# NT_SolarModule1.net
KiCad netlist of a schematic drawn in EAGLE
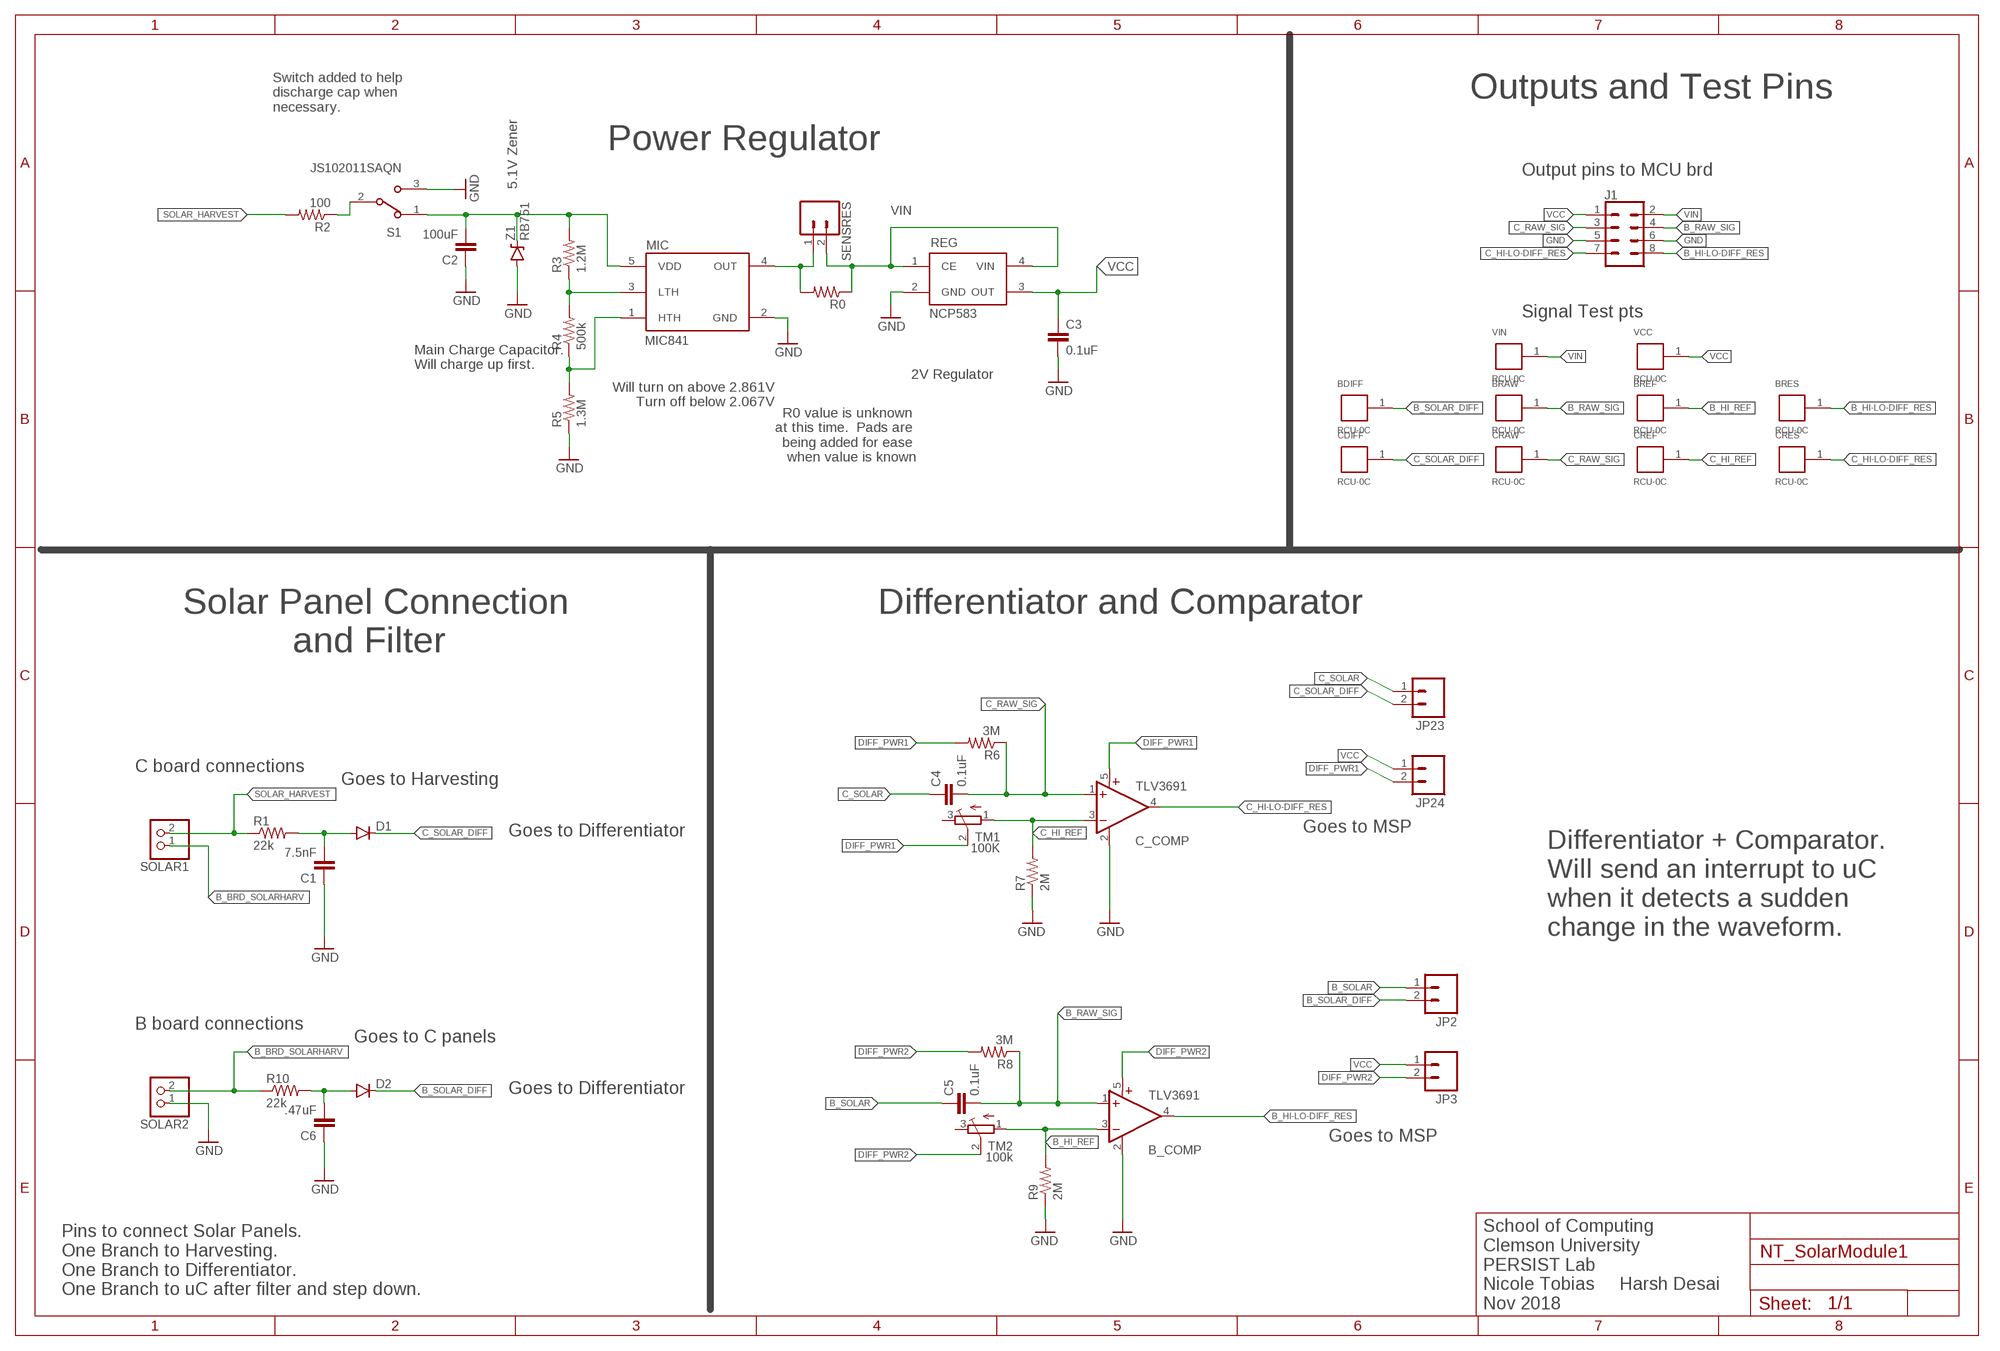
[diagram p0: schematic, sheet 1]

(export (version "E")
  (design (tool "Eeschema 10.0.6"))
  (components
    (comp (ref "BDIFF")
      (value "RCU-0C")
      (footprint "eagle-import:TE_RCU-0C")
      (fields
        (field (name "COMMENT") "RCU-0C _1625854-3_")
        (field (name "MF") "TE Connectivity")
        (field (name "TOLERANCE") "0%")
      )
      (libsource (lib "eagle-import") (part "RCU-0C"))
    )
    (comp (ref "BRAW")
      (value "RCU-0C")
      (footprint "eagle-import:TE_RCU-0C")
      (fields
        (field (name "COMMENT") "RCU-0C _1625854-3_")
        (field (name "MF") "TE Connectivity")
        (field (name "TOLERANCE") "0%")
      )
      (libsource (lib "eagle-import") (part "RCU-0C"))
    )
    (comp (ref "BREF")
      (value "RCU-0C")
      (footprint "eagle-import:TE_RCU-0C")
      (fields
        (field (name "COMMENT") "RCU-0C _1625854-3_")
        (field (name "MF") "TE Connectivity")
        (field (name "TOLERANCE") "0%")
      )
      (libsource (lib "eagle-import") (part "RCU-0C"))
    )
    (comp (ref "BRES")
      (value "RCU-0C")
      (footprint "eagle-import:TE_RCU-0C")
      (fields
        (field (name "COMMENT") "RCU-0C _1625854-3_")
        (field (name "MF") "TE Connectivity")
        (field (name "TOLERANCE") "0%")
      )
      (libsource (lib "eagle-import") (part "RCU-0C"))
    )
    (comp (ref "B_COMP")
      (value "TLV3691")
      (footprint "eagle-import:SC70-5")
      (libsource (lib "eagle-import") (part "TLV3691"))
    )
    (comp (ref "C1")
      (value "7.5nF")
      (footprint "eagle-import:0603-CAP")
      (libsource (lib "eagle-import") (part "CAP0603-CAP"))
    )
    (comp (ref "C2")
      (value "100uF")
      (footprint "eagle-import:0603-CAP")
      (libsource (lib "eagle-import") (part "CAP0603-CAP"))
    )
    (comp (ref "C3")
      (value "0.1uF")
      (footprint "eagle-import:0603-CAP")
      (libsource (lib "eagle-import") (part "CAP0603-CAP"))
    )
    (comp (ref "C4")
      (value "0.1uF")
      (footprint "eagle-import:0603-CAP")
      (libsource (lib "eagle-import") (part "CAP0603-CAP"))
    )
    (comp (ref "C5")
      (value "0.1uF")
      (footprint "eagle-import:0603-CAP")
      (libsource (lib "eagle-import") (part "CAP0603-CAP"))
    )
    (comp (ref "C6")
      (value ".47uF")
      (footprint "eagle-import:0603-CAP")
      (libsource (lib "eagle-import") (part "CAP0603-CAP"))
    )
    (comp (ref "CDIFF")
      (value "RCU-0C")
      (footprint "eagle-import:TE_RCU-0C")
      (fields
        (field (name "COMMENT") "RCU-0C _1625854-3_")
        (field (name "MF") "TE Connectivity")
        (field (name "TOLERANCE") "0%")
      )
      (libsource (lib "eagle-import") (part "RCU-0C"))
    )
    (comp (ref "CRAW")
      (value "RCU-0C")
      (footprint "eagle-import:TE_RCU-0C")
      (fields
        (field (name "COMMENT") "RCU-0C _1625854-3_")
        (field (name "MF") "TE Connectivity")
        (field (name "TOLERANCE") "0%")
      )
      (libsource (lib "eagle-import") (part "RCU-0C"))
    )
    (comp (ref "CREF")
      (value "RCU-0C")
      (footprint "eagle-import:TE_RCU-0C")
      (fields
        (field (name "COMMENT") "RCU-0C _1625854-3_")
        (field (name "MF") "TE Connectivity")
        (field (name "TOLERANCE") "0%")
      )
      (libsource (lib "eagle-import") (part "RCU-0C"))
    )
    (comp (ref "CRES")
      (value "RCU-0C")
      (footprint "eagle-import:TE_RCU-0C")
      (fields
        (field (name "COMMENT") "RCU-0C _1625854-3_")
        (field (name "MF") "TE Connectivity")
        (field (name "TOLERANCE") "0%")
      )
      (libsource (lib "eagle-import") (part "RCU-0C"))
    )
    (comp (ref "C_COMP")
      (value "TLV3691")
      (footprint "eagle-import:SC70-5")
      (libsource (lib "eagle-import") (part "TLV3691"))
    )
    (comp (ref "D1")
      (value "DIODESOD523")
      (footprint "eagle-import:SOD523")
      (libsource (lib "eagle-import") (part "DIODESOD523"))
    )
    (comp (ref "D2")
      (value "DIODESOD523")
      (footprint "eagle-import:SOD523")
      (libsource (lib "eagle-import") (part "DIODESOD523"))
    )
    (comp (ref "J1")
      (value "CONN_04X2")
      (footprint "eagle-import:2X4")
      (libsource (lib "eagle-import") (part "CONN_04X2"))
    )
    (comp (ref "JP2")
      (value "M02")
      (footprint "eagle-import:1X02-1.27MM")
      (libsource (lib "eagle-import") (part "M02"))
    )
    (comp (ref "JP3")
      (value "M02")
      (footprint "eagle-import:1X02-1.27MM")
      (libsource (lib "eagle-import") (part "M02"))
    )
    (comp (ref "JP23")
      (value "M02")
      (footprint "eagle-import:1X02-1.27MM")
      (libsource (lib "eagle-import") (part "M02"))
    )
    (comp (ref "JP24")
      (value "M02")
      (footprint "eagle-import:1X02-1.27MM")
      (libsource (lib "eagle-import") (part "M02"))
    )
    (comp (ref "MIC")
      (value "MIC841")
      (footprint "eagle-import:SC70-5")
      (libsource (lib "eagle-import") (part "MIC841"))
    )
    (comp (ref "R0")
      (value "RESISTOR0603")
      (footprint "eagle-import:0603-RES")
      (libsource (lib "eagle-import") (part "RESISTOR0603"))
    )
    (comp (ref "R1")
      (value "22k")
      (footprint "eagle-import:0603-RES")
      (libsource (lib "eagle-import") (part "RESISTOR0603"))
    )
    (comp (ref "R2")
      (value "100")
      (footprint "eagle-import:0603-RES")
      (libsource (lib "eagle-import") (part "RESISTOR0603"))
    )
    (comp (ref "R3")
      (value "1.2M")
      (footprint "eagle-import:0603-RES")
      (libsource (lib "eagle-import") (part "RESISTOR0603"))
    )
    (comp (ref "R4")
      (value "500k")
      (footprint "eagle-import:0603-RES")
      (libsource (lib "eagle-import") (part "RESISTOR0603"))
    )
    (comp (ref "R5")
      (value "1.3M")
      (footprint "eagle-import:0603-RES")
      (libsource (lib "eagle-import") (part "RESISTOR0603"))
    )
    (comp (ref "R6")
      (value "3M")
      (footprint "eagle-import:0603-RES")
      (libsource (lib "eagle-import") (part "RESISTOR0603"))
    )
    (comp (ref "R7")
      (value "2M")
      (footprint "eagle-import:0603-RES")
      (libsource (lib "eagle-import") (part "RESISTOR0603"))
    )
    (comp (ref "R8")
      (value "3M")
      (footprint "eagle-import:0603-RES")
      (libsource (lib "eagle-import") (part "RESISTOR0603"))
    )
    (comp (ref "R9")
      (value "2M")
      (footprint "eagle-import:0603-RES")
      (libsource (lib "eagle-import") (part "RESISTOR0603"))
    )
    (comp (ref "R10")
      (value "22k")
      (footprint "eagle-import:0603-RES")
      (libsource (lib "eagle-import") (part "RESISTOR0603"))
    )
    (comp (ref "REG")
      (value "NCP583")
      (footprint "eagle-import:SC82-AB_1PRIMARY")
      (libsource (lib "eagle-import") (part "NCP583"))
    )
    (comp (ref "S1")
      (value "JS102011SAQN")
      (footprint "eagle-import:SW_JS102011SAQN")
      (fields (field (name "MF") "C&K Components"))
      (libsource (lib "eagle-import") (part "JS102011SAQN"))
    )
    (comp (ref "SENSRES")
      (value "CONN_02")
      (footprint "eagle-import:1X02")
      (libsource (lib "eagle-import") (part "CONN_02"))
    )
    (comp (ref "SOLAR1")
      (value "PINHD-1X2")
      (footprint "eagle-import:1X02")
      (libsource (lib "eagle-import") (part "PINHD-1X2"))
    )
    (comp (ref "SOLAR2")
      (value "PINHD-1X2")
      (footprint "eagle-import:1X02")
      (libsource (lib "eagle-import") (part "PINHD-1X2"))
    )
    (comp (ref "TM1")
      (value "100K")
      (footprint "eagle-import:TC33X")
      (libsource (lib "eagle-import") (part "TRIMPOTTC33X"))
    )
    (comp (ref "TM2")
      (value "100k")
      (footprint "eagle-import:TC33X")
      (libsource (lib "eagle-import") (part "TRIMPOTTC33X"))
    )
    (comp (ref "VCC")
      (value "RCU-0C")
      (footprint "eagle-import:TE_RCU-0C")
      (fields
        (field (name "COMMENT") "RCU-0C _1625854-3_")
        (field (name "MF") "TE Connectivity")
        (field (name "TOLERANCE") "0%")
      )
      (libsource (lib "eagle-import") (part "RCU-0C"))
    )
    (comp (ref "VIN")
      (value "RCU-0C")
      (footprint "eagle-import:TE_RCU-0C")
      (fields
        (field (name "COMMENT") "RCU-0C _1625854-3_")
        (field (name "MF") "TE Connectivity")
        (field (name "TOLERANCE") "0%")
      )
      (libsource (lib "eagle-import") (part "RCU-0C"))
    )
    (comp (ref "Z1")
      (value "RB751")
      (footprint "eagle-import:SOD-523")
      (libsource (lib "eagle-import") (part "DIODE-ZENER"))
    )
  )
  (nets
    (net (code "1") (name "B_BRD_SOLARHARV") (class "Default")
      (node (ref "R10") (pin "1") (pinfunction "1_1") (pintype "passive"))
      (node (ref "SOLAR1") (pin "1") (pinfunction "1_1") (pintype "passive"))
      (node (ref "SOLAR2") (pin "2") (pinfunction "2_2") (pintype "passive"))
    )
    (net (code "2") (name "B_HI-LO-DIFF_RES") (class "Default")
      (node (ref "BRES") (pin "1") (pinfunction "1_1") (pintype "passive"))
      (node (ref "B_COMP") (pin "4") (pinfunction "OUT_4") (pintype "output"))
      (node (ref "J1") (pin "8") (pinfunction "8_8") (pintype "passive"))
    )
    (net (code "3") (name "B_HI_REF") (class "Default")
      (node (ref "BREF") (pin "1") (pinfunction "1_1") (pintype "passive"))
      (node (ref "B_COMP") (pin "3") (pinfunction "-IN_3") (pintype "input"))
      (node (ref "R9") (pin "2") (pinfunction "2_2") (pintype "passive"))
      (node (ref "TM2") (pin "1") (pinfunction "A_1") (pintype "passive"))
    )
    (net (code "4") (name "B_RAW_SIG") (class "Default")
      (node (ref "BRAW") (pin "1") (pinfunction "1_1") (pintype "passive"))
      (node (ref "B_COMP") (pin "1") (pinfunction "+IN_1") (pintype "input"))
      (node (ref "C5") (pin "2") (pinfunction "2_2") (pintype "passive"))
      (node (ref "J1") (pin "4") (pinfunction "4_4") (pintype "passive"))
      (node (ref "R8") (pin "1") (pinfunction "1_1") (pintype "passive"))
    )
    (net (code "5") (name "B_SOLAR") (class "Default")
      (node (ref "C5") (pin "1") (pinfunction "1_1") (pintype "passive"))
      (node (ref "JP2") (pin "1") (pinfunction "1_1") (pintype "passive"))
    )
    (net (code "6") (name "B_SOLAR_DIFF") (class "Default")
      (node (ref "BDIFF") (pin "1") (pinfunction "1_1") (pintype "passive"))
      (node (ref "D2") (pin "C") (pinfunction "C_C") (pintype "passive"))
      (node (ref "JP2") (pin "2") (pinfunction "2_2") (pintype "passive"))
    )
    (net (code "7") (name "C_HI-LO-DIFF_RES") (class "Default")
      (node (ref "CRES") (pin "1") (pinfunction "1_1") (pintype "passive"))
      (node (ref "C_COMP") (pin "4") (pinfunction "OUT_4") (pintype "output"))
      (node (ref "J1") (pin "7") (pinfunction "7_7") (pintype "passive"))
    )
    (net (code "8") (name "C_HI_REF") (class "Default")
      (node (ref "CREF") (pin "1") (pinfunction "1_1") (pintype "passive"))
      (node (ref "C_COMP") (pin "3") (pinfunction "-IN_3") (pintype "input"))
      (node (ref "R7") (pin "2") (pinfunction "2_2") (pintype "passive"))
      (node (ref "TM1") (pin "1") (pinfunction "A_1") (pintype "passive"))
    )
    (net (code "9") (name "C_RAW_SIG") (class "Default")
      (node (ref "C4") (pin "2") (pinfunction "2_2") (pintype "passive"))
      (node (ref "CRAW") (pin "1") (pinfunction "1_1") (pintype "passive"))
      (node (ref "C_COMP") (pin "1") (pinfunction "+IN_1") (pintype "input"))
      (node (ref "J1") (pin "3") (pinfunction "3_3") (pintype "passive"))
      (node (ref "R6") (pin "1") (pinfunction "1_1") (pintype "passive"))
    )
    (net (code "10") (name "C_SOLAR") (class "Default")
      (node (ref "C4") (pin "1") (pinfunction "1_1") (pintype "passive"))
      (node (ref "JP23") (pin "1") (pinfunction "1_1") (pintype "passive"))
    )
    (net (code "11") (name "C_SOLAR_DIFF") (class "Default")
      (node (ref "CDIFF") (pin "1") (pinfunction "1_1") (pintype "passive"))
      (node (ref "D1") (pin "C") (pinfunction "C_C") (pintype "passive"))
      (node (ref "JP23") (pin "2") (pinfunction "2_2") (pintype "passive"))
    )
    (net (code "12") (name "DIFF_PWR1") (class "Default")
      (node (ref "C_COMP") (pin "5") (pinfunction "V+_5") (pintype "power_in"))
      (node (ref "JP24") (pin "2") (pinfunction "2_2") (pintype "passive"))
      (node (ref "R6") (pin "2") (pinfunction "2_2") (pintype "passive"))
      (node (ref "TM1") (pin "2") (pinfunction "S_2") (pintype "passive"))
    )
    (net (code "13") (name "DIFF_PWR2") (class "Default")
      (node (ref "B_COMP") (pin "5") (pinfunction "V+_5") (pintype "power_in"))
      (node (ref "JP3") (pin "2") (pinfunction "2_2") (pintype "passive"))
      (node (ref "R8") (pin "2") (pinfunction "2_2") (pintype "passive"))
      (node (ref "TM2") (pin "2") (pinfunction "S_2") (pintype "passive"))
    )
    (net (code "14") (name "GND") (class "Default")
      (node (ref "B_COMP") (pin "2") (pinfunction "GND_2") (pintype "power_in"))
      (node (ref "C1") (pin "1") (pinfunction "1_1") (pintype "passive"))
      (node (ref "C2") (pin "1") (pinfunction "1_1") (pintype "passive"))
      (node (ref "C3") (pin "2") (pinfunction "2_2") (pintype "passive"))
      (node (ref "C6") (pin "1") (pinfunction "1_1") (pintype "passive"))
      (node (ref "C_COMP") (pin "2") (pinfunction "GND_2") (pintype "power_in"))
      (node (ref "J1") (pin "5") (pinfunction "5_5") (pintype "passive"))
      (node (ref "J1") (pin "6") (pinfunction "6_6") (pintype "passive"))
      (node (ref "MIC") (pin "2") (pinfunction "GND_2") (pintype "bidirectional"))
      (node (ref "R5") (pin "1") (pinfunction "1_1") (pintype "passive"))
      (node (ref "R7") (pin "1") (pinfunction "1_1") (pintype "passive"))
      (node (ref "R9") (pin "1") (pinfunction "1_1") (pintype "passive"))
      (node (ref "REG") (pin "2") (pinfunction "GND_2") (pintype "bidirectional"))
      (node (ref "S1") (pin "3") (pinfunction "3_3") (pintype "passive"))
      (node (ref "SOLAR2") (pin "1") (pinfunction "1_1") (pintype "passive"))
      (node (ref "Z1") (pin "ANODE") (pinfunction "A_ANODE") (pintype "passive"))
    )
    (net (code "15") (name "Net-(C1-Pad2)") (class "Default")
      (node (ref "C1") (pin "2") (pinfunction "2_2") (pintype "passive"))
      (node (ref "D1") (pin "A") (pinfunction "A_A") (pintype "passive"))
      (node (ref "R1") (pin "2") (pinfunction "2_2") (pintype "passive"))
    )
    (net (code "16") (name "Net-(C6-Pad2)") (class "Default")
      (node (ref "C6") (pin "2") (pinfunction "2_2") (pintype "passive"))
      (node (ref "D2") (pin "A") (pinfunction "A_A") (pintype "passive"))
      (node (ref "R10") (pin "2") (pinfunction "2_2") (pintype "passive"))
    )
    (net (code "17") (name "Net-(MIC-HTH)") (class "Default")
      (node (ref "MIC") (pin "1") (pinfunction "HTH_1") (pintype "bidirectional"))
      (node (ref "R4") (pin "1") (pinfunction "1_1") (pintype "passive"))
      (node (ref "R5") (pin "2") (pinfunction "2_2") (pintype "passive"))
    )
    (net (code "18") (name "Net-(MIC-LTH)") (class "Default")
      (node (ref "MIC") (pin "3") (pinfunction "LTH_3") (pintype "bidirectional"))
      (node (ref "R3") (pin "1") (pinfunction "1_1") (pintype "passive"))
      (node (ref "R4") (pin "2") (pinfunction "2_2") (pintype "passive"))
    )
    (net (code "19") (name "Net-(MIC-OUT)") (class "Default")
      (node (ref "MIC") (pin "4") (pinfunction "OUT_4") (pintype "bidirectional"))
      (node (ref "R0") (pin "2") (pinfunction "2_2") (pintype "passive"))
      (node (ref "SENSRES") (pin "1") (pinfunction "1_1") (pintype "passive"))
    )
    (net (code "20") (name "Net-(MIC-VDD)") (class "Default")
      (node (ref "C2") (pin "2") (pinfunction "2_2") (pintype "passive"))
      (node (ref "MIC") (pin "5") (pinfunction "VDD_5") (pintype "bidirectional"))
      (node (ref "R3") (pin "2") (pinfunction "2_2") (pintype "passive"))
      (node (ref "S1") (pin "1") (pinfunction "1_1") (pintype "passive"))
      (node (ref "Z1") (pin "CATHODE") (pinfunction "C_CATHODE") (pintype "passive"))
    )
    (net (code "21") (name "Net-(R2-Pad1)") (class "Default")
      (node (ref "R2") (pin "1") (pinfunction "1_1") (pintype "passive"))
      (node (ref "S1") (pin "2") (pinfunction "2_2") (pintype "passive"))
    )
    (net (code "22") (name "SOLAR_HARVEST") (class "Default")
      (node (ref "R1") (pin "1") (pinfunction "1_1") (pintype "passive"))
      (node (ref "R2") (pin "2") (pinfunction "2_2") (pintype "passive"))
      (node (ref "SOLAR1") (pin "2") (pinfunction "2_2") (pintype "passive"))
    )
    (net (code "23") (name "VCC") (class "Default")
      (node (ref "C3") (pin "1") (pinfunction "1_1") (pintype "passive"))
      (node (ref "J1") (pin "1") (pinfunction "1_1") (pintype "passive"))
      (node (ref "JP24") (pin "1") (pinfunction "1_1") (pintype "passive"))
      (node (ref "JP3") (pin "1") (pinfunction "1_1") (pintype "passive"))
      (node (ref "REG") (pin "3") (pinfunction "OUT_3") (pintype "bidirectional"))
      (node (ref "VCC") (pin "1") (pinfunction "1_1") (pintype "passive"))
    )
    (net (code "24") (name "VIN") (class "Default")
      (node (ref "J1") (pin "2") (pinfunction "2_2") (pintype "passive"))
      (node (ref "R0") (pin "1") (pinfunction "1_1") (pintype "passive"))
      (node (ref "REG") (pin "1") (pinfunction "CE_1") (pintype "bidirectional"))
      (node (ref "REG") (pin "4") (pinfunction "VIN_4") (pintype "bidirectional"))
      (node (ref "SENSRES") (pin "2") (pinfunction "2_2") (pintype "passive"))
      (node (ref "VIN") (pin "1") (pinfunction "1_1") (pintype "passive"))
    )
    (net (code "25") (name "unconnected-(TM1-E-Pad3)") (class "Default")
      (node (ref "TM1") (pin "3") (pinfunction "E_3") (pintype "passive"))
    )
    (net (code "26") (name "unconnected-(TM2-E-Pad3)") (class "Default")
      (node (ref "TM2") (pin "3") (pinfunction "E_3") (pintype "passive"))
    )
  )
)
